# DCDC_stepdown.net
KiCad netlist of a schematic drawn in Altium Designer
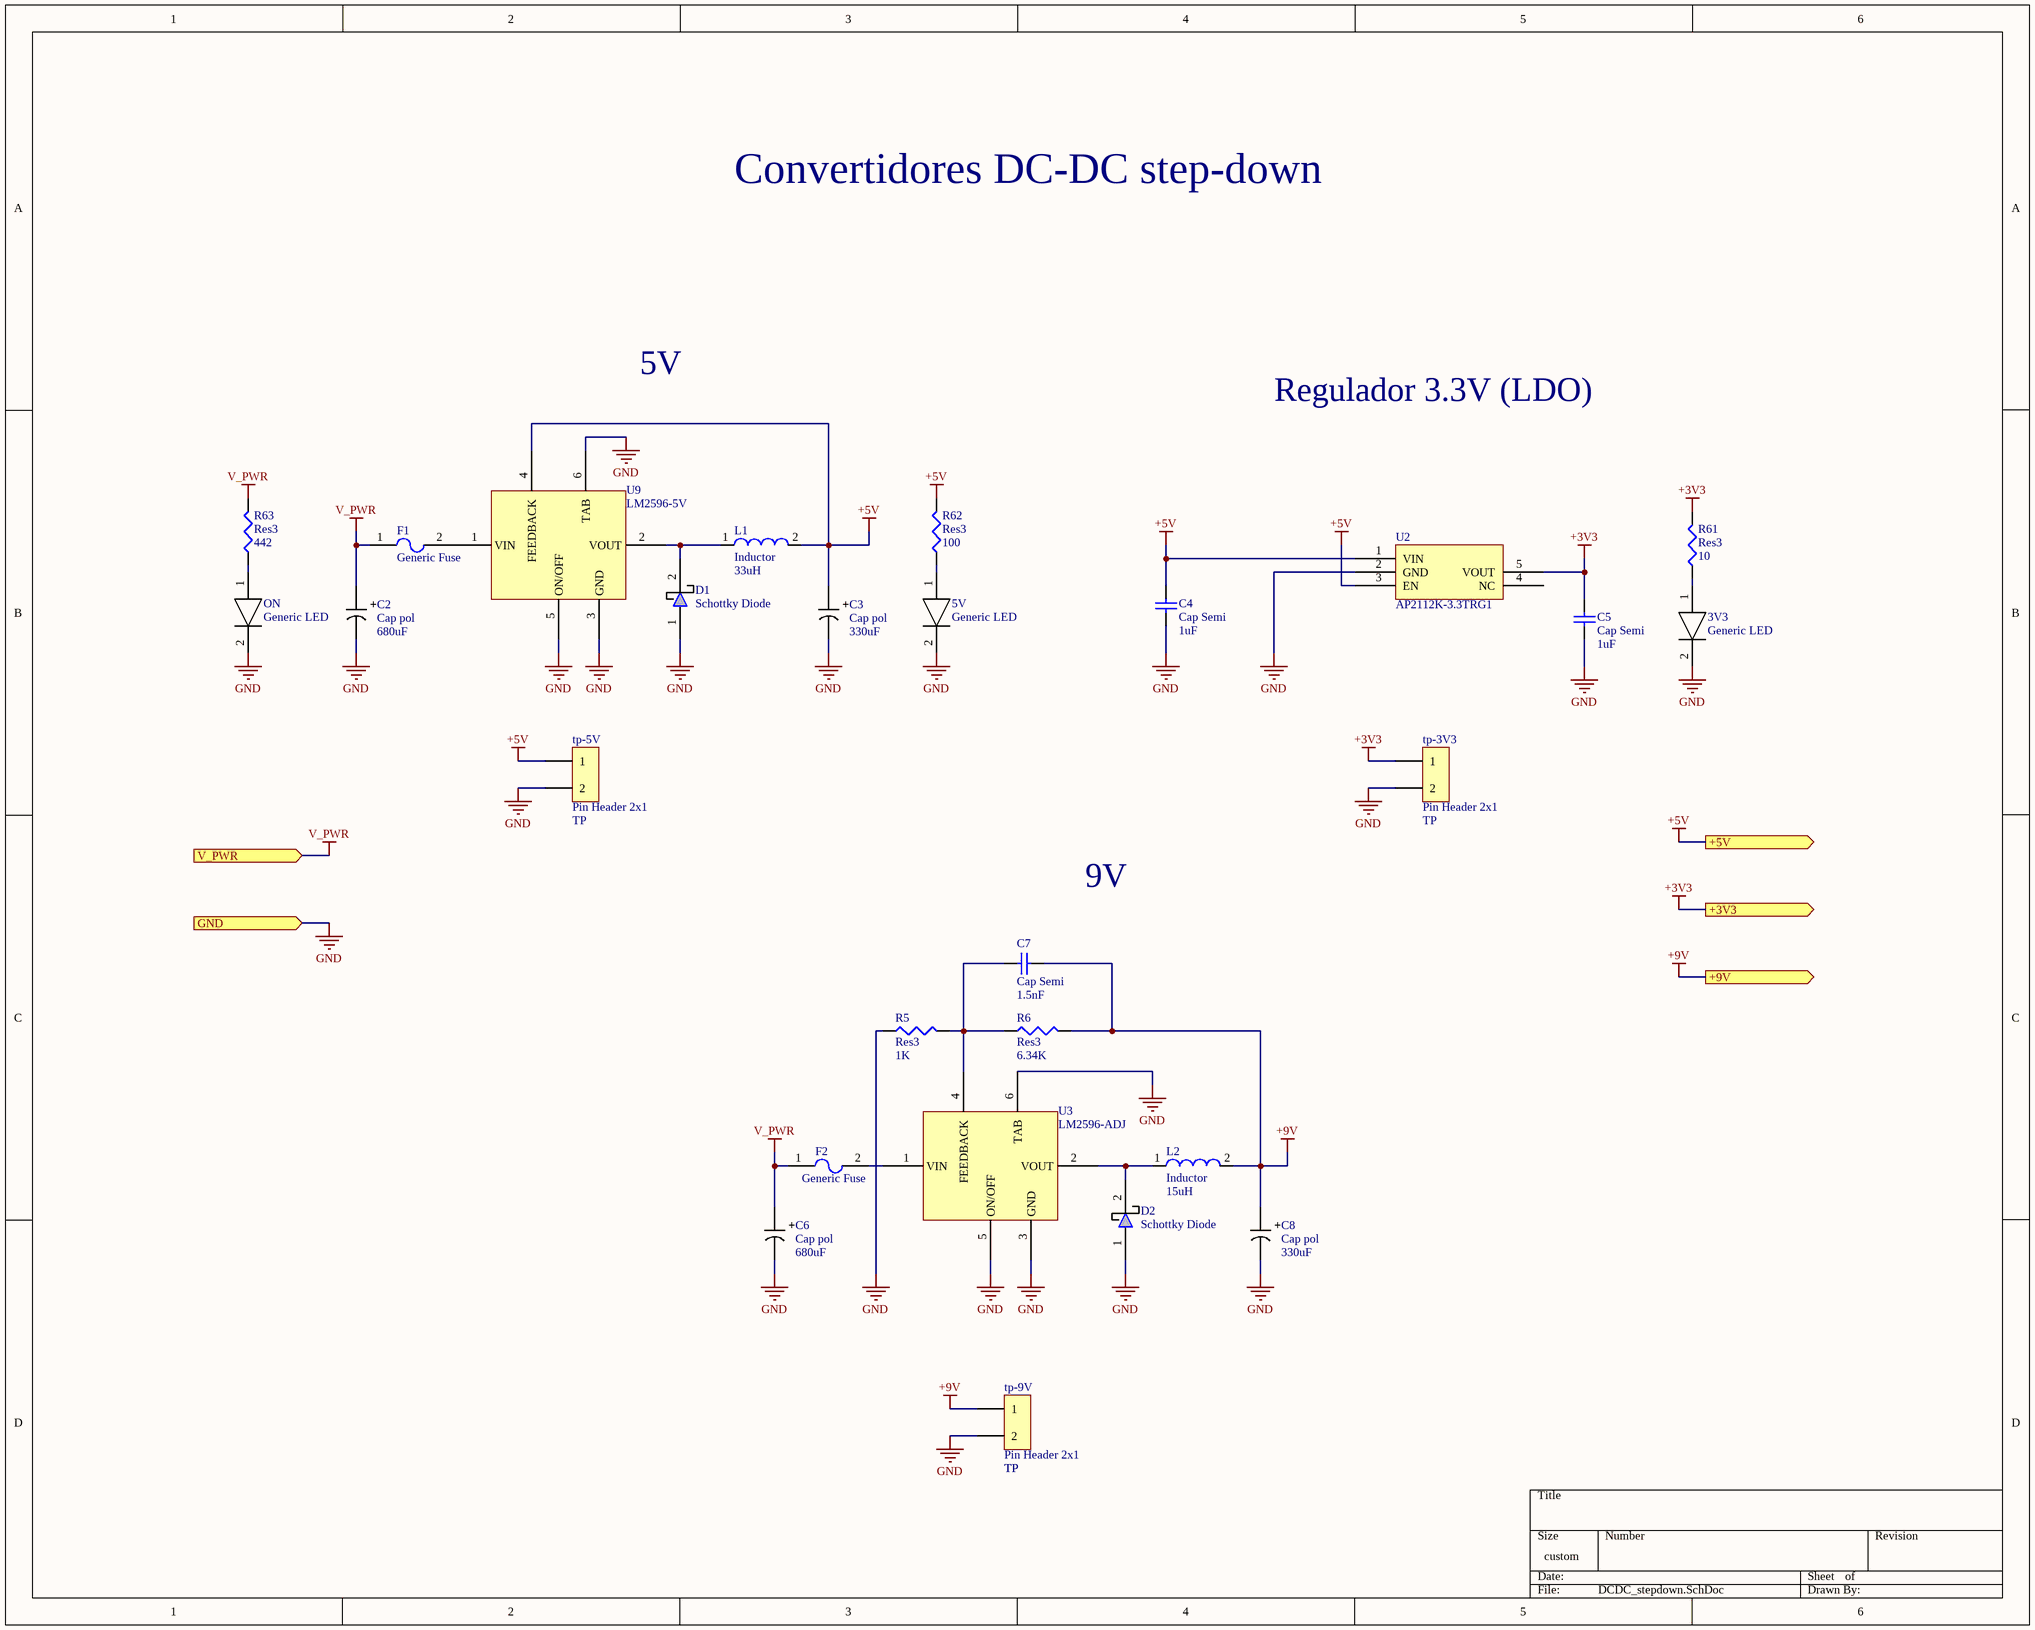
[diagram p0: DCDC_stepdown.SchDoc]

(export (version "E")
  (design (tool "Eeschema 10.0.6"))
  (components
    (comp (ref "3V3")
      (value "Generic LED")
      (footprint "LED0603")
      (description "Generic LED SMD")
      (fields
        (field (name "MANUFACTURER") "Lite-On")
        (field (name "MANUFACTURER PART NUMBER") "LTST-C191TGKT")
      )
      (libsource (lib "IoWLabs") (part "LED"))
    )
    (comp (ref "5V")
      (value "Generic LED")
      (footprint "LED0603")
      (description "Generic LED SMD")
      (fields
        (field (name "MANUFACTURER") "Lite-On")
        (field (name "MANUFACTURER PART NUMBER") "LTST-C191TGKT")
      )
      (libsource (lib "IoWLabs") (part "LED"))
    )
    (comp (ref "C2")
      (value "Cap pol")
      (footprint "CAP_SMD_Electrolytic_13.5x13.5")
      (description "Electrolytic Aluminium Capacitor")
      (fields
        (field (name "MANUFACTURER") "PANASONIC")
        (field (name "MANUFACTURER PART NUMBER") "EEEFK1V681AQ")
        (field (name "ALTIUM_VALUE") "680uF")
      )
      (libsource (lib "IoWLabs") (part "Cap pol"))
    )
    (comp (ref "C3")
      (value "Cap pol")
      (footprint "CAP_SMD_Electrolytic_10x10")
      (description "Electrolytic Aluminium Capacitor")
      (fields
        (field (name "MANUFACTURER") "PANASONIC")
        (field (name "MANUFACTURER PART NUMBER") "EEE1VA331UAP")
        (field (name "ALTIUM_VALUE") "330uF")
      )
      (libsource (lib "IoWLabs") (part "Cap pol"))
    )
    (comp (ref "C4")
      (value "Cap Semi")
      (footprint "1608[0603]")
      (description "Capacitor (Semiconductor SIM Model)")
      (fields
        (field (name "ALTIUM_VALUE") "1uF")
        (field (name "MANUFACTURER") "Samsung Electro-Mechanics")
        (field (name "MANUFACTURER PART NUMBER") "CL10B105KO8NNNC")
        (field (name "PUBLISHER") "Altium Limited")
      )
      (libsource (lib "Miscellaneous Devices") (part "Cap Semi"))
    )
    (comp (ref "C5")
      (value "Cap Semi")
      (footprint "1608[0603]")
      (description "Capacitor (Semiconductor SIM Model)")
      (fields
        (field (name "ALTIUM_VALUE") "1uF")
        (field (name "MANUFACTURER") "Samsung Electro-Mechanics")
        (field (name "MANUFACTURER PART NUMBER") "CL10B105KO8NNNC")
        (field (name "PUBLISHER") "Altium Limited")
      )
      (libsource (lib "Miscellaneous Devices") (part "Cap Semi"))
    )
    (comp (ref "C6")
      (value "Cap pol")
      (footprint "CAP_SMD_Electrolytic_13.5x13.5")
      (description "Electrolytic Aluminium Capacitor")
      (fields
        (field (name "MANUFACTURER") "PANASONIC")
        (field (name "MANUFACTURER PART NUMBER") "EEEFK1V681AQ")
        (field (name "ALTIUM_VALUE") "680uF")
      )
      (libsource (lib "IoWLabs") (part "Cap pol"))
    )
    (comp (ref "C7")
      (value "Cap Semi")
      (footprint "1608[0603]")
      (description "Capacitor (Semiconductor SIM Model)")
      (fields
        (field (name "ALTIUM_VALUE") "1.5nF")
        (field (name "MANUFACTURER") "Walsin Tech Corp")
        (field (name "MANUFACTURER PART NUMBER") "0603B152K500")
        (field (name "PUBLISHER") "Altium Limited")
      )
      (libsource (lib "Miscellaneous Devices") (part "Cap Semi"))
    )
    (comp (ref "C8")
      (value "Cap pol")
      (footprint "CAP_SMD_Electrolytic_10x10")
      (description "Electrolytic Aluminium Capacitor")
      (fields
        (field (name "MANUFACTURER") "PANASONIC")
        (field (name "MANUFACTURER PART NUMBER") "EEE1VA331UAP")
        (field (name "ALTIUM_VALUE") "330uF")
      )
      (libsource (lib "IoWLabs") (part "Cap pol"))
    )
    (comp (ref "D1")
      (value "Schottky Diode")
      (footprint "SMB_L4.6-W3.6-LS5.3-RD")
      (description "Schottky Diodes")
      (fields
        (field (name "MANUFACTURER") "MCC(Micro Commercial Components)")
        (field (name "MANUFACTURER PART NUMBER") "SK32B-LTP")
      )
      (libsource (lib "IoWLabs") (part "Schottky Diode"))
    )
    (comp (ref "D2")
      (value "Schottky Diode")
      (footprint "SMB_L4.6-W3.6-LS5.3-RD")
      (description "Schottky Diodes")
      (fields
        (field (name "MANUFACTURER") "MCC(Micro Commercial Components)")
        (field (name "MANUFACTURER PART NUMBER") "SK32B-LTP")
      )
      (libsource (lib "IoWLabs") (part "Schottky Diode"))
    )
    (comp (ref "F1")
      (value "Generic Fuse")
      (footprint "F1206")
      (description "SMD Fuse")
      (fields (field (name "MANUFACTURER") "AEM") (field (name "MANUFACTURER PART NUMBER") "F1206VH4500TM"))
      (libsource (lib "IoWLabs") (part "FUSE"))
    )
    (comp (ref "F2")
      (value "Generic Fuse")
      (footprint "F1206")
      (description "SMD Fuse")
      (fields (field (name "MANUFACTURER") "AEM") (field (name "MANUFACTURER PART NUMBER") "F1206VH4500TM"))
      (libsource (lib "IoWLabs") (part "FUSE"))
    )
    (comp (ref "L1")
      (value "Inductor")
      (footprint "IND-SMD_L12.5-W12.5_SMDRS1275")
      (description "Inductor SMD")
      (fields
        (field (name "MANUFACTURER") "GLE")
        (field (name "MANUFACTURER PART NUMBER") "GCRH127M-330MC")
        (field (name "ALTIUM_VALUE") "33uH")
      )
      (libsource (lib "IoWLabs") (part "Inductor"))
    )
    (comp (ref "L2")
      (value "Inductor")
      (footprint "IND-SMD_L8.0-W8.0")
      (description "Inductor SMD")
      (fields
        (field (name "MANUFACTURER") "3L COILS")
        (field (name "MANUFACTURER PART NUMBER") "SNR8040K-150M")
        (field (name "ALTIUM_VALUE") "15uH")
      )
      (libsource (lib "IoWLabs") (part "Inductor"))
    )
    (comp (ref "ON")
      (value "Generic LED")
      (footprint "LED0603")
      (description "Generic LED SMD")
      (fields
        (field (name "MANUFACTURER") "Lite-On")
        (field (name "MANUFACTURER PART NUMBER") "LTST-C191TGKT")
      )
      (libsource (lib "IoWLabs") (part "LED"))
    )
    (comp (ref "R5")
      (value "Res3")
      (footprint "J1-0603")
      (description "Resistor")
      (fields
        (field (name "ALTIUM_VALUE") "1K")
        (field (name "MANUFACTURER") "KAMAYA")
        (field (name "MANUFACTURER PART NUMBER") "RMC16K102FTP")
        (field (name "PUBLISHER") "Altium Limited")
      )
      (libsource (lib "Miscellaneous Devices") (part "Res3"))
    )
    (comp (ref "R6")
      (value "Res3")
      (footprint "J1-0603")
      (description "Resistor")
      (fields
        (field (name "ALTIUM_VALUE") "6.34K")
        (field (name "MANUFACTURER") "YAGEO")
        (field (name "MANUFACTURER PART NUMBER") "RC0603FR-076K34L")
        (field (name "PUBLISHER") "Altium Limited")
      )
      (libsource (lib "Miscellaneous Devices") (part "Res3"))
    )
    (comp (ref "R61")
      (value "Res3")
      (footprint "J1-0603")
      (description "Resistor")
      (fields
        (field (name "ALTIUM_VALUE") "10")
        (field (name "MANUFACTURER PART NUMBER") "RC0603FR-0710RL")
        (field (name "MANUFACTURER") "YAGEO")
        (field (name "PUBLISHER") "Altium Limited")
      )
      (libsource (lib "Miscellaneous Devices") (part "Res3"))
    )
    (comp (ref "R62")
      (value "Res3")
      (footprint "J1-0603")
      (description "Resistor")
      (fields
        (field (name "ALTIUM_VALUE") "100")
        (field (name "MANUFACTURER PART NUMBER") "RC0603FR-07100RL")
        (field (name "MANUFACTURER") "YAGEO")
        (field (name "PUBLISHER") "Altium Limited")
      )
      (libsource (lib "Miscellaneous Devices") (part "Res3"))
    )
    (comp (ref "R63")
      (value "Res3")
      (footprint "J1-0603")
      (description "Resistor")
      (fields
        (field (name "ALTIUM_VALUE") "442")
        (field (name "MANUFACTURER PART NUMBER") "AC0603FR-07442RL")
        (field (name "MANUFACTURER") "YAGEO")
        (field (name "PUBLISHER") "Altium Limited")
      )
      (libsource (lib "Miscellaneous Devices") (part "Res3"))
    )
    (comp (ref "tp-3V3")
      (value "Pin Header 2x1")
      (footprint "HDR-TH_P2.54-H-M_A2541WV-2P")
      (description "Pin Header 2pos, 1 row, 2.54 pitch")
      (fields
        (field (name "MANUFACTURER") "CJT(Changjiang Connectors)")
        (field (name "MANUFACTURER PART NUMBER") "A2541WV-2P")
      )
      (libsource (lib "IoWLabsConnectors") (part "Header - 2x1c"))
    )
    (comp (ref "tp-5V")
      (value "Pin Header 2x1")
      (footprint "HDR-TH_P2.54-H-M_A2541WV-2P")
      (description "Pin Header 2pos, 1 row, 2.54 pitch")
      (fields
        (field (name "MANUFACTURER") "CJT(Changjiang Connectors)")
        (field (name "MANUFACTURER PART NUMBER") "A2541WV-2P")
      )
      (libsource (lib "IoWLabsConnectors") (part "Header - 2x1c"))
    )
    (comp (ref "tp-9V")
      (value "Pin Header 2x1")
      (footprint "HDR-TH_P2.54-H-M_A2541WV-2P")
      (description "Pin Header 2pos, 1 row, 2.54 pitch")
      (fields
        (field (name "MANUFACTURER") "CJT(Changjiang Connectors)")
        (field (name "MANUFACTURER PART NUMBER") "A2541WV-2P")
      )
      (libsource (lib "IoWLabsConnectors") (part "Header - 2x1c"))
    )
    (comp (ref "U2")
      (value "AP2112K-3.3TRG1")
      (footprint "SOT25-5")
      (description "600mA CMOS LDO REGULATOR WITH ENABLE")
      (fields (field (name "MANUFACTURER") "DIODES"))
      (libsource (lib "IoWLabs") (part "AP2112K-3.3"))
    )
    (comp (ref "U3")
      (value "LM2596-ADJ")
      (footprint "TO-263-5")
      (description "DC-DC Converters Step-Down Adjustable 1 4.5V 40V 1.2V 37V 3A TO-263-5 RoHS")
      (fields
        (field (name "MANUFACTURER") "Texas Instruments")
        (field (name "MANUFACTURER PART NUMBER") "LM2596SX-ADJ/NOPB")
      )
      (libsource (lib "IoWLabs") (part "LM2596-ADJ"))
    )
    (comp (ref "U9")
      (value "LM2596-5V")
      (footprint "TO-263-5")
      (description "Step-Down Positive Fixed 1 3A 150kHz TO-263-5 DC-DC Converters RoHS")
      (fields
        (field (name "MANUFACTURER") "HTC Korea TAEJIN Tech")
        (field (name "MANUFACTURER PART NUMBER") "LM2596R-5.0")
      )
      (libsource (lib "IoWLabs") (part "LM2596-5V"))
    )
  )
  (nets
    (net (code "1") (name "+3V3") (class "Default")
      (node (ref "C5") (pin "2") (pinfunction "2_2") (pintype "passive"))
      (node (ref "R61") (pin "2") (pinfunction "2_2") (pintype "passive"))
      (node (ref "U2") (pin "5") (pinfunction "VOUT_5") (pintype "passive"))
      (node (ref "tp-3V3") (pin "1") (pinfunction "1_1") (pintype "passive"))
    )
    (net (code "2") (name "+5V") (class "Default")
      (node (ref "C3") (pin "2") (pinfunction "2_2") (pintype "passive"))
      (node (ref "C4") (pin "2") (pinfunction "2_2") (pintype "passive"))
      (node (ref "L1") (pin "2") (pinfunction "2_2") (pintype "passive"))
      (node (ref "R62") (pin "2") (pinfunction "2_2") (pintype "passive"))
      (node (ref "U2") (pin "1") (pinfunction "VIN_1") (pintype "passive"))
      (node (ref "U2") (pin "3") (pinfunction "EN_3") (pintype "passive"))
      (node (ref "U9") (pin "4") (pinfunction "FEEDBACK_4") (pintype "passive"))
      (node (ref "tp-5V") (pin "1") (pinfunction "1_1") (pintype "passive"))
    )
    (net (code "3") (name "+9V") (class "Default")
      (node (ref "C7") (pin "2") (pinfunction "2_2") (pintype "passive"))
      (node (ref "C8") (pin "2") (pinfunction "2_2") (pintype "passive"))
      (node (ref "L2") (pin "2") (pinfunction "2_2") (pintype "passive"))
      (node (ref "R6") (pin "2") (pinfunction "2_2") (pintype "passive"))
      (node (ref "tp-9V") (pin "1") (pinfunction "1_1") (pintype "passive"))
    )
    (net (code "4") (name "GND") (class "Default")
      (node (ref "3V3") (pin "2") (pinfunction "2_2") (pintype "passive"))
      (node (ref "5V") (pin "2") (pinfunction "2_2") (pintype "passive"))
      (node (ref "C2") (pin "1") (pinfunction "1_1") (pintype "passive"))
      (node (ref "C3") (pin "1") (pinfunction "1_1") (pintype "passive"))
      (node (ref "C4") (pin "1") (pinfunction "1_1") (pintype "passive"))
      (node (ref "C5") (pin "1") (pinfunction "1_1") (pintype "passive"))
      (node (ref "C6") (pin "1") (pinfunction "1_1") (pintype "passive"))
      (node (ref "C8") (pin "1") (pinfunction "1_1") (pintype "passive"))
      (node (ref "D1") (pin "1") (pinfunction "+_1") (pintype "passive"))
      (node (ref "D2") (pin "1") (pinfunction "+_1") (pintype "passive"))
      (node (ref "ON") (pin "2") (pinfunction "2_2") (pintype "passive"))
      (node (ref "R5") (pin "1") (pinfunction "1_1") (pintype "passive"))
      (node (ref "U2") (pin "2") (pinfunction "GND_2") (pintype "passive"))
      (node (ref "U3") (pin "3") (pinfunction "GND_3") (pintype "passive"))
      (node (ref "U3") (pin "5") (pinfunction "ON/OFF_5") (pintype "passive"))
      (node (ref "U3") (pin "6") (pinfunction "TAB_6") (pintype "passive"))
      (node (ref "U9") (pin "3") (pinfunction "GND_3") (pintype "passive"))
      (node (ref "U9") (pin "5") (pinfunction "ON/OFF_5") (pintype "passive"))
      (node (ref "U9") (pin "6") (pinfunction "TAB_6") (pintype "passive"))
      (node (ref "tp-3V3") (pin "2") (pinfunction "2_2") (pintype "passive"))
      (node (ref "tp-5V") (pin "2") (pinfunction "2_2") (pintype "passive"))
      (node (ref "tp-9V") (pin "2") (pinfunction "2_2") (pintype "passive"))
    )
    (net (code "5") (name "Net-(3V3-Pad1)") (class "Default")
      (node (ref "3V3") (pin "1") (pinfunction "1_1") (pintype "passive"))
      (node (ref "R61") (pin "1") (pinfunction "1_1") (pintype "passive"))
    )
    (net (code "6") (name "Net-(5V-Pad1)") (class "Default")
      (node (ref "5V") (pin "1") (pinfunction "1_1") (pintype "passive"))
      (node (ref "R62") (pin "1") (pinfunction "1_1") (pintype "passive"))
    )
    (net (code "7") (name "Net-(D1--)") (class "Default")
      (node (ref "D1") (pin "2") (pinfunction "-_2") (pintype "passive"))
      (node (ref "L1") (pin "1") (pinfunction "1_1") (pintype "passive"))
      (node (ref "U9") (pin "2") (pinfunction "VOUT_2") (pintype "passive"))
    )
    (net (code "8") (name "Net-(D2--)") (class "Default")
      (node (ref "D2") (pin "2") (pinfunction "-_2") (pintype "passive"))
      (node (ref "L2") (pin "1") (pinfunction "1_1") (pintype "passive"))
      (node (ref "U3") (pin "2") (pinfunction "VOUT_2") (pintype "passive"))
    )
    (net (code "9") (name "Net-(ON-Pad1)") (class "Default")
      (node (ref "ON") (pin "1") (pinfunction "1_1") (pintype "passive"))
      (node (ref "R63") (pin "1") (pinfunction "1_1") (pintype "passive"))
    )
    (net (code "10") (name "Net-(U3-FEEDBACK)") (class "Default")
      (node (ref "C7") (pin "1") (pinfunction "1_1") (pintype "passive"))
      (node (ref "R5") (pin "2") (pinfunction "2_2") (pintype "passive"))
      (node (ref "R6") (pin "1") (pinfunction "1_1") (pintype "passive"))
      (node (ref "U3") (pin "4") (pinfunction "FEEDBACK_4") (pintype "passive"))
    )
    (net (code "11") (name "Net-(U3-VIN)") (class "Default")
      (node (ref "F2") (pin "2") (pinfunction "2_2") (pintype "passive"))
      (node (ref "U3") (pin "1") (pinfunction "VIN_1") (pintype "passive"))
    )
    (net (code "12") (name "Net-(U9-VIN)") (class "Default")
      (node (ref "F1") (pin "2") (pinfunction "2_2") (pintype "passive"))
      (node (ref "U9") (pin "1") (pinfunction "VIN_1") (pintype "passive"))
    )
    (net (code "13") (name "V_PWR") (class "Default")
      (node (ref "C2") (pin "2") (pinfunction "2_2") (pintype "passive"))
      (node (ref "C6") (pin "2") (pinfunction "2_2") (pintype "passive"))
      (node (ref "F1") (pin "1") (pinfunction "1_1") (pintype "passive"))
      (node (ref "F2") (pin "1") (pinfunction "1_1") (pintype "passive"))
      (node (ref "R63") (pin "2") (pinfunction "2_2") (pintype "passive"))
    )
    (net (code "14") (name "unconnected-(U2-NC-Pad4)") (class "Default")
      (node (ref "U2") (pin "4") (pinfunction "NC_4") (pintype "passive"))
    )
  )
)
